# moveWiFi.net
KiCad netlist of a schematic drawn in Altium Designer
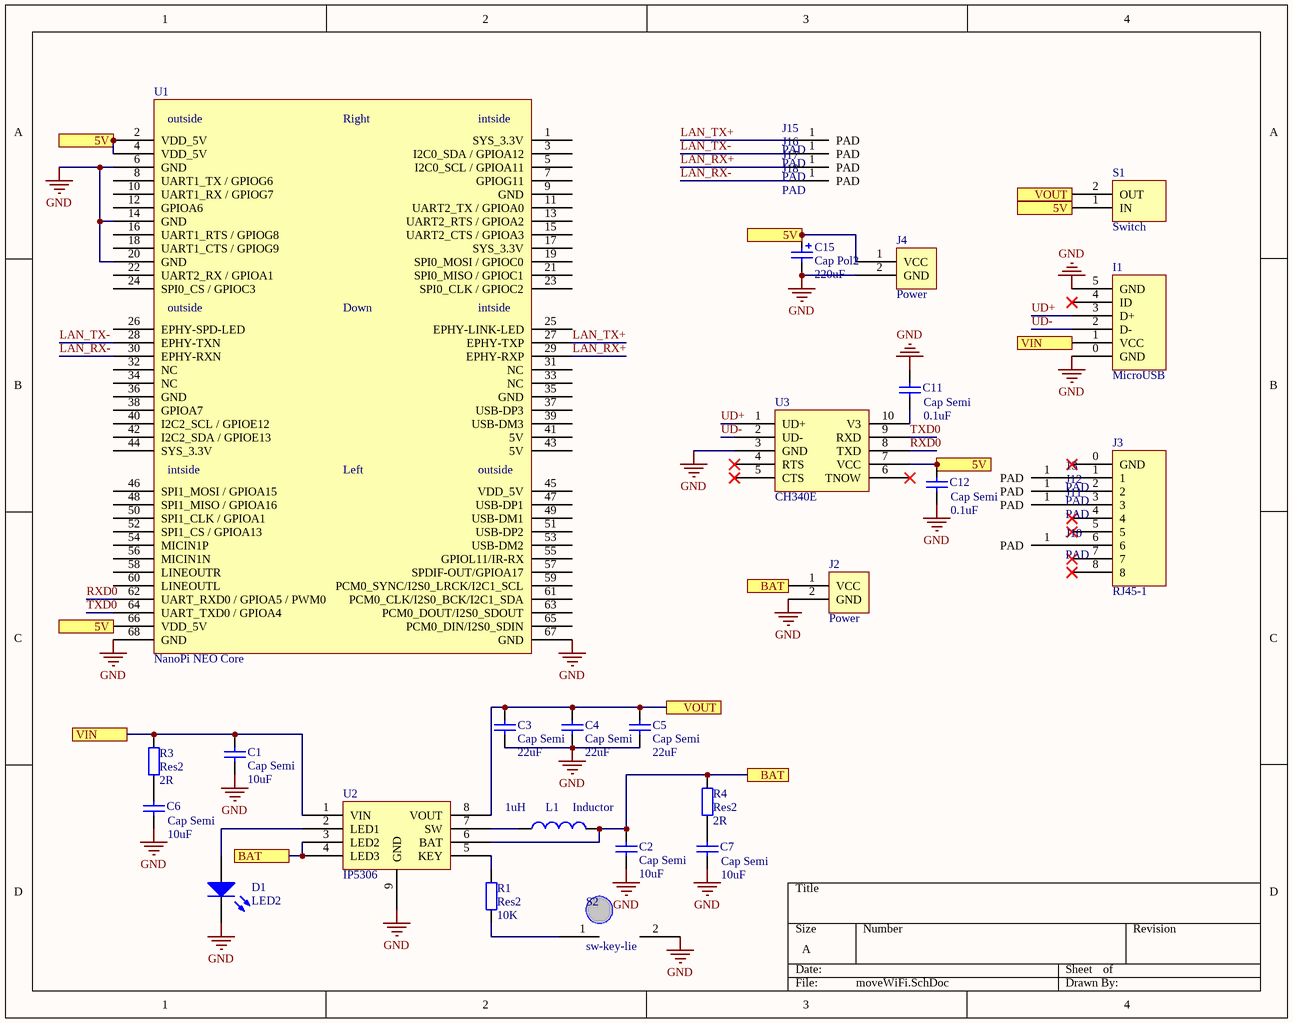
[diagram p0: moveWiFi.SchDoc]

(export (version "E")
  (design (tool "Eeschema 10.0.6"))
  (components
    (comp (ref "13") (value "PAD") (footprint "PAD") (libsource (lib "GavinPCBLib") (part "PAD")))
    (comp (ref "C1")
      (value "Cap Semi")
      (footprint "我的元件库01:C0805")
      (description "Capacitor (Semiconductor SIM Model)")
      (fields (field (name "ALTIUM_VALUE") "10uF") (field (name "PUBLISHER") "Altium Limited"))
      (libsource (lib "Miscellaneous Devices") (part "Cap Semi"))
    )
    (comp (ref "C2")
      (value "Cap Semi")
      (footprint "我的元件库01:C0805")
      (description "Capacitor (Semiconductor SIM Model)")
      (fields (field (name "ALTIUM_VALUE") "10uF") (field (name "PUBLISHER") "Altium Limited"))
      (libsource (lib "Miscellaneous Devices") (part "Cap Semi"))
    )
    (comp (ref "C3")
      (value "Cap Semi")
      (footprint "我的元件库01:C0805")
      (description "Capacitor (Semiconductor SIM Model)")
      (fields (field (name "ALTIUM_VALUE") "22uF") (field (name "PUBLISHER") "Altium Limited"))
      (libsource (lib "Miscellaneous Devices") (part "Cap Semi"))
    )
    (comp (ref "C4")
      (value "Cap Semi")
      (footprint "我的元件库01:C0805")
      (description "Capacitor (Semiconductor SIM Model)")
      (fields (field (name "ALTIUM_VALUE") "22uF") (field (name "PUBLISHER") "Altium Limited"))
      (libsource (lib "Miscellaneous Devices") (part "Cap Semi"))
    )
    (comp (ref "C5")
      (value "Cap Semi")
      (footprint "我的元件库01:C0805")
      (description "Capacitor (Semiconductor SIM Model)")
      (fields (field (name "ALTIUM_VALUE") "22uF") (field (name "PUBLISHER") "Altium Limited"))
      (libsource (lib "Miscellaneous Devices") (part "Cap Semi"))
    )
    (comp (ref "C6")
      (value "Cap Semi")
      (footprint "我的元件库01:C0805")
      (description "Capacitor (Semiconductor SIM Model)")
      (fields (field (name "ALTIUM_VALUE") "10uF") (field (name "PUBLISHER") "Altium Limited"))
      (libsource (lib "Miscellaneous Devices") (part "Cap Semi"))
    )
    (comp (ref "C7")
      (value "Cap Semi")
      (footprint "我的元件库01:C0805")
      (description "Capacitor (Semiconductor SIM Model)")
      (fields (field (name "ALTIUM_VALUE") "10uF") (field (name "PUBLISHER") "Altium Limited"))
      (libsource (lib "Miscellaneous Devices") (part "Cap Semi"))
    )
    (comp (ref "C11")
      (value "Cap Semi")
      (footprint "C0603")
      (description "Capacitor (Semiconductor SIM Model)")
      (fields (field (name "ALTIUM_VALUE") "0.1uF") (field (name "PUBLISHER") "Altium Limited"))
      (libsource (lib "Miscellaneous Devices") (part "Cap Semi"))
    )
    (comp (ref "C12")
      (value "Cap Semi")
      (footprint "C0603")
      (description "Capacitor (Semiconductor SIM Model)")
      (fields (field (name "ALTIUM_VALUE") "0.1uF") (field (name "PUBLISHER") "Altium Limited"))
      (libsource (lib "Miscellaneous Devices") (part "Cap Semi"))
    )
    (comp (ref "C15")
      (value "Cap Pol2")
      (footprint "C7343")
      (description "Polarized Capacitor (Axial)")
      (fields (field (name "ALTIUM_VALUE") "220uF") (field (name "PUBLISHER") "Altium Limited"))
      (libsource (lib "Miscellaneous Devices") (part "Cap Pol2"))
    )
    (comp (ref "D1")
      (value "LED2")
      (footprint "R0603")
      (description "Typical RED, GREEN, YELLOW, AMBER GaAs LED")
      (fields (field (name "PUBLISHER") "Altium Limited"))
      (libsource (lib "Miscellaneous Devices") (part "LED2"))
    )
    (comp (ref "I1")
      (value "MicroUSB")
      (footprint "MicroUSB")
      (libsource (lib "GavinPCBLib") (part "MicroUSB"))
    )
    (comp (ref "J2") (value "Power") (footprint "Power 2") (libsource (lib "GavinPCBLib") (part "Power")))
    (comp (ref "J3") (value "RJ45-1") (footprint "RG45-3") (libsource (lib "GavinPCBLib") (part "RJ45-3")))
    (comp (ref "J4") (value "Power") (footprint "Power 2") (libsource (lib "GavinPCBLib") (part "Power")))
    (comp (ref "J10") (value "PAD") (footprint "PAD") (libsource (lib "GavinPCBLib") (part "PAD")))
    (comp (ref "J11") (value "PAD") (footprint "PAD") (libsource (lib "GavinPCBLib") (part "PAD")))
    (comp (ref "J12") (value "PAD") (footprint "PAD") (libsource (lib "GavinPCBLib") (part "PAD")))
    (comp (ref "J15") (value "PAD") (footprint "PAD") (libsource (lib "GavinPCBLib") (part "PAD")))
    (comp (ref "J16") (value "PAD") (footprint "PAD") (libsource (lib "GavinPCBLib") (part "PAD")))
    (comp (ref "J17") (value "PAD") (footprint "PAD") (libsource (lib "GavinPCBLib") (part "PAD")))
    (comp (ref "J18") (value "PAD") (footprint "PAD") (libsource (lib "GavinPCBLib") (part "PAD")))
    (comp (ref "L1")
      (value "Inductor")
      (footprint "L0630")
      (fields (field (name "ALTIUM_VALUE") "1uH") (field (name "PUBLISHER") "Altium Limited"))
      (libsource (lib "Miscellaneous Devices") (part "Inductor"))
    )
    (comp (ref "R1")
      (value "Res2")
      (footprint "R0603")
      (description "Resistor")
      (fields (field (name "ALTIUM_VALUE") "10K") (field (name "PUBLISHER") "Altium Limited"))
      (libsource (lib "Miscellaneous Devices") (part "Res2"))
    )
    (comp (ref "R3")
      (value "Res2")
      (footprint "R0603")
      (description "Resistor")
      (fields (field (name "ALTIUM_VALUE") "2R") (field (name "PUBLISHER") "Altium Limited"))
      (libsource (lib "Miscellaneous Devices") (part "Res2"))
    )
    (comp (ref "R4")
      (value "Res2")
      (footprint "R0603")
      (description "Resistor")
      (fields (field (name "ALTIUM_VALUE") "2R") (field (name "PUBLISHER") "Altium Limited"))
      (libsource (lib "Miscellaneous Devices") (part "Res2"))
    )
    (comp (ref "S1") (value "Switch") (footprint "SwitchA2") (libsource (lib "GavinPCBLib") (part "Switch2")))
    (comp (ref "S2")
      (value "sw-key-lie")
      (footprint "Key_lie")
      (libsource (lib "GavinPCBLib") (part "sw-key-lie"))
    )
    (comp (ref "U1") (value "NanoPi NEO Core") (libsource (lib "GavinPCBLib") (part "NanoPi_NEO_Core")))
    (comp (ref "U2") (value "IP5306") (footprint "eSOP8") (libsource (lib "GavinPCBLib") (part "IP5306")))
    (comp (ref "U3") (value "CH340E") (footprint "MSOP-10") (libsource (lib "GavinPCBLib") (part "CH340E")))
  )
  (nets
    (net (code "1") (name "/5V") (class "Default")
      (node (ref "C12") (pin "2") (pinfunction "2_2") (pintype "passive"))
      (node (ref "C15") (pin "1") (pinfunction "1_1") (pintype "passive"))
      (node (ref "J4") (pin "1") (pinfunction "VCC_1") (pintype "passive"))
      (node (ref "S1") (pin "1") (pinfunction "IN_1") (pintype "passive"))
      (node (ref "U1") (pin "2") (pinfunction "VDD_5V_2") (pintype "passive"))
      (node (ref "U1") (pin "4") (pinfunction "VDD_5V_4") (pintype "passive"))
      (node (ref "U1") (pin "66") (pinfunction "VDD_5V_66") (pintype "passive"))
      (node (ref "U3") (pin "7") (pinfunction "VCC_7") (pintype "passive"))
    )
    (net (code "2") (name "/BAT") (class "Default")
      (node (ref "C2") (pin "2") (pinfunction "2_2") (pintype "passive"))
      (node (ref "J2") (pin "1") (pinfunction "VCC_1") (pintype "passive"))
      (node (ref "L1") (pin "2") (pinfunction "2_2") (pintype "passive"))
      (node (ref "R4") (pin "2") (pinfunction "2_2") (pintype "passive"))
      (node (ref "U2") (pin "3") (pinfunction "LED2_3") (pintype "passive"))
      (node (ref "U2") (pin "4") (pinfunction "LED3_4") (pintype "passive"))
      (node (ref "U2") (pin "6") (pinfunction "BAT_6") (pintype "passive"))
    )
    (net (code "3") (name "/LAN_RX+") (class "Default")
      (node (ref "J17") (pin "1") (pinfunction "PAD_1") (pintype "passive"))
      (node (ref "U1") (pin "29") (pinfunction "EPHY-RXP_29") (pintype "passive"))
    )
    (net (code "4") (name "/LAN_RX-") (class "Default")
      (node (ref "J18") (pin "1") (pinfunction "PAD_1") (pintype "passive"))
      (node (ref "U1") (pin "30") (pinfunction "EPHY-RXN_30") (pintype "passive"))
    )
    (net (code "5") (name "/LAN_TX+") (class "Default")
      (node (ref "J15") (pin "1") (pinfunction "PAD_1") (pintype "passive"))
      (node (ref "U1") (pin "27") (pinfunction "EPHY-TXP_27") (pintype "passive"))
    )
    (net (code "6") (name "/LAN_TX-") (class "Default")
      (node (ref "J16") (pin "1") (pinfunction "PAD_1") (pintype "passive"))
      (node (ref "U1") (pin "28") (pinfunction "EPHY-TXN_28") (pintype "passive"))
    )
    (net (code "7") (name "/RXD0") (class "Default")
      (node (ref "U1") (pin "62") (pinfunction "UART_RXD0_/_GPIOA5_/_PWM0_62") (pintype "passive"))
      (node (ref "U3") (pin "8") (pinfunction "TXD_8") (pintype "passive"))
    )
    (net (code "8") (name "/TXD0") (class "Default")
      (node (ref "U1") (pin "64") (pinfunction "UART_TXD0_/_GPIOA4_64") (pintype "passive"))
      (node (ref "U3") (pin "9") (pinfunction "RXD_9") (pintype "passive"))
    )
    (net (code "9") (name "/UD+") (class "Default")
      (node (ref "I1") (pin "3") (pinfunction "D+_3") (pintype "passive"))
      (node (ref "U3") (pin "1") (pinfunction "UD+_1") (pintype "passive"))
    )
    (net (code "10") (name "/UD-") (class "Default")
      (node (ref "I1") (pin "2") (pinfunction "D-_2") (pintype "passive"))
      (node (ref "U3") (pin "2") (pinfunction "UD-_2") (pintype "passive"))
    )
    (net (code "11") (name "/VIN") (class "Default")
      (node (ref "C1") (pin "2") (pinfunction "2_2") (pintype "passive"))
      (node (ref "I1") (pin "1") (pinfunction "VCC_1") (pintype "passive"))
      (node (ref "R3") (pin "2") (pinfunction "2_2") (pintype "passive"))
      (node (ref "U2") (pin "1") (pinfunction "VIN_1") (pintype "passive"))
    )
    (net (code "12") (name "/VOUT") (class "Default")
      (node (ref "C3") (pin "2") (pinfunction "2_2") (pintype "passive"))
      (node (ref "C4") (pin "2") (pinfunction "2_2") (pintype "passive"))
      (node (ref "C5") (pin "2") (pinfunction "2_2") (pintype "passive"))
      (node (ref "S1") (pin "2") (pinfunction "OUT_2") (pintype "passive"))
      (node (ref "U2") (pin "8") (pinfunction "VOUT_8") (pintype "passive"))
    )
    (net (code "13") (name "GND") (class "Default")
      (node (ref "C1") (pin "1") (pinfunction "1_1") (pintype "passive"))
      (node (ref "C11") (pin "2") (pinfunction "2_2") (pintype "passive"))
      (node (ref "C12") (pin "1") (pinfunction "1_1") (pintype "passive"))
      (node (ref "C15") (pin "2") (pinfunction "2_2") (pintype "passive"))
      (node (ref "C2") (pin "1") (pinfunction "1_1") (pintype "passive"))
      (node (ref "C3") (pin "1") (pinfunction "1_1") (pintype "passive"))
      (node (ref "C4") (pin "1") (pinfunction "1_1") (pintype "passive"))
      (node (ref "C5") (pin "1") (pinfunction "1_1") (pintype "passive"))
      (node (ref "C6") (pin "1") (pinfunction "1_1") (pintype "passive"))
      (node (ref "C7") (pin "1") (pinfunction "1_1") (pintype "passive"))
      (node (ref "D1") (pin "2") (pinfunction "K_2") (pintype "passive"))
      (node (ref "I1") (pin "0") (pinfunction "GND_0") (pintype "passive"))
      (node (ref "I1") (pin "5") (pinfunction "GND_5") (pintype "passive"))
      (node (ref "J2") (pin "2") (pinfunction "GND_2") (pintype "passive"))
      (node (ref "J4") (pin "2") (pinfunction "GND_2") (pintype "passive"))
      (node (ref "S2") (pin "2") (pintype "passive"))
      (node (ref "U1") (pin "14") (pinfunction "GND_14") (pintype "passive"))
      (node (ref "U1") (pin "20") (pinfunction "GND_20") (pintype "passive"))
      (node (ref "U1") (pin "6") (pinfunction "GND_6") (pintype "passive"))
      (node (ref "U1") (pin "67") (pinfunction "GND_67") (pintype "passive"))
      (node (ref "U1") (pin "68") (pinfunction "GND_68") (pintype "passive"))
      (node (ref "U2") (pin "9") (pinfunction "GND_9") (pintype "passive"))
      (node (ref "U3") (pin "3") (pinfunction "GND_3") (pintype "passive"))
    )
    (net (code "14") (name "Net-(13-PAD)") (class "Default")
      (node (ref "13") (pin "1") (pinfunction "PAD_1") (pintype "passive"))
      (node (ref "J3") (pin "1") (pinfunction "1_1") (pintype "passive"))
    )
    (net (code "15") (name "Net-(C6-Pad2)") (class "Default")
      (node (ref "C6") (pin "2") (pinfunction "2_2") (pintype "passive"))
      (node (ref "R3") (pin "1") (pinfunction "1_1") (pintype "passive"))
    )
    (net (code "16") (name "Net-(C7-Pad2)") (class "Default")
      (node (ref "C7") (pin "2") (pinfunction "2_2") (pintype "passive"))
      (node (ref "R4") (pin "1") (pinfunction "1_1") (pintype "passive"))
    )
    (net (code "17") (name "Net-(D1-A)") (class "Default")
      (node (ref "D1") (pin "1") (pinfunction "A_1") (pintype "passive"))
      (node (ref "U2") (pin "2") (pinfunction "LED1_2") (pintype "passive"))
    )
    (net (code "18") (name "Net-(J10-PAD)") (class "Default")
      (node (ref "J10") (pin "1") (pinfunction "PAD_1") (pintype "passive"))
      (node (ref "J3") (pin "6") (pinfunction "6_6") (pintype "passive"))
    )
    (net (code "19") (name "Net-(J11-PAD)") (class "Default")
      (node (ref "J11") (pin "1") (pinfunction "PAD_1") (pintype "passive"))
      (node (ref "J3") (pin "3") (pinfunction "3_3") (pintype "passive"))
    )
    (net (code "20") (name "Net-(J12-PAD)") (class "Default")
      (node (ref "J12") (pin "1") (pinfunction "PAD_1") (pintype "passive"))
      (node (ref "J3") (pin "2") (pinfunction "2_2") (pintype "passive"))
    )
    (net (code "21") (name "Net-(R1-Pad1)") (class "Default")
      (node (ref "R1") (pin "1") (pinfunction "1_1") (pintype "passive"))
      (node (ref "S2") (pin "1") (pintype "passive"))
    )
    (net (code "22") (name "Net-(U2-KEY)") (class "Default")
      (node (ref "R1") (pin "2") (pinfunction "2_2") (pintype "passive"))
      (node (ref "U2") (pin "5") (pinfunction "KEY_5") (pintype "passive"))
    )
    (net (code "23") (name "Net-(U2-SW)") (class "Default")
      (node (ref "L1") (pin "1") (pinfunction "1_1") (pintype "passive"))
      (node (ref "U2") (pin "7") (pinfunction "SW_7") (pintype "passive"))
    )
    (net (code "24") (name "Net-(U3-V3)") (class "Default")
      (node (ref "C11") (pin "1") (pinfunction "1_1") (pintype "passive"))
      (node (ref "U3") (pin "10") (pinfunction "V3_10") (pintype "passive"))
    )
    (net (code "25") (name "unconnected-(I1-ID-Pad4)") (class "Default")
      (node (ref "I1") (pin "4") (pinfunction "ID_4") (pintype "passive+no_connect"))
    )
    (net (code "26") (name "unconnected-(J3-GND-Pad0)") (class "Default")
      (node (ref "J3") (pin "0") (pinfunction "GND_0") (pintype "passive+no_connect"))
    )
    (net (code "27") (name "unconnected-(J3-Pad4)") (class "Default")
      (node (ref "J3") (pin "4") (pinfunction "4_4") (pintype "passive+no_connect"))
    )
    (net (code "28") (name "unconnected-(J3-Pad5)") (class "Default")
      (node (ref "J3") (pin "5") (pinfunction "5_5") (pintype "passive+no_connect"))
    )
    (net (code "29") (name "unconnected-(J3-Pad7)") (class "Default")
      (node (ref "J3") (pin "7") (pinfunction "7_7") (pintype "passive+no_connect"))
    )
    (net (code "30") (name "unconnected-(J3-Pad8)") (class "Default")
      (node (ref "J3") (pin "8") (pinfunction "8_8") (pintype "passive+no_connect"))
    )
    (net (code "31") (name "unconnected-(U1-5V-Pad41)") (class "Default")
      (node (ref "U1") (pin "41") (pinfunction "5V_41") (pintype "passive"))
    )
    (net (code "32") (name "unconnected-(U1-5V-Pad43)") (class "Default")
      (node (ref "U1") (pin "43") (pinfunction "5V_43") (pintype "passive"))
    )
    (net (code "33") (name "unconnected-(U1-EPHY-LINK-LED-Pad25)") (class "Default")
      (node (ref "U1") (pin "25") (pinfunction "EPHY-LINK-LED_25") (pintype "passive"))
    )
    (net (code "34") (name "unconnected-(U1-EPHY-SPD-LED-Pad26)") (class "Default")
      (node (ref "U1") (pin "26") (pinfunction "EPHY-SPD-LED_26") (pintype "passive"))
    )
    (net (code "35") (name "unconnected-(U1-GND-Pad9)") (class "Default")
      (node (ref "U1") (pin "9") (pinfunction "GND_9") (pintype "passive"))
    )
    (net (code "36") (name "unconnected-(U1-GND-Pad35)") (class "Default")
      (node (ref "U1") (pin "35") (pinfunction "GND_35") (pintype "passive"))
    )
    (net (code "37") (name "unconnected-(U1-GND-Pad36)") (class "Default")
      (node (ref "U1") (pin "36") (pinfunction "GND_36") (pintype "passive"))
    )
    (net (code "38") (name "unconnected-(U1-GPIOA6-Pad12)") (class "Default")
      (node (ref "U1") (pin "12") (pinfunction "GPIOA6_12") (pintype "passive"))
    )
    (net (code "39") (name "unconnected-(U1-GPIOA7-Pad38)") (class "Default")
      (node (ref "U1") (pin "38") (pinfunction "GPIOA7_38") (pintype "passive"))
    )
    (net (code "40") (name "unconnected-(U1-GPIOG11-Pad7)") (class "Default")
      (node (ref "U1") (pin "7") (pinfunction "GPIOG11_7") (pintype "passive"))
    )
    (net (code "41") (name "unconnected-(U1-GPIOL11{slash}IR-RX-Pad55)") (class "Default")
      (node (ref "U1") (pin "55") (pinfunction "GPIOL11/IR-RX_55") (pintype "passive"))
    )
    (net (code "42") (name "unconnected-(U1-I2C0_SCL_{slash}_GPIOA11-Pad5)") (class "Default")
      (node (ref "U1") (pin "5") (pinfunction "I2C0_SCL_/_GPIOA11_5") (pintype "passive"))
    )
    (net (code "43") (name "unconnected-(U1-I2C0_SDA_{slash}_GPIOA12-Pad3)") (class "Default")
      (node (ref "U1") (pin "3") (pinfunction "I2C0_SDA_/_GPIOA12_3") (pintype "passive"))
    )
    (net (code "44") (name "unconnected-(U1-I2C2_SCL_{slash}_GPIOE12-Pad40)") (class "Default")
      (node (ref "U1") (pin "40") (pinfunction "I2C2_SCL_/_GPIOE12_40") (pintype "passive"))
    )
    (net (code "45") (name "unconnected-(U1-I2C2_SDA_{slash}_GPIOE13-Pad42)") (class "Default")
      (node (ref "U1") (pin "42") (pinfunction "I2C2_SDA_/_GPIOE13_42") (pintype "passive"))
    )
    (net (code "46") (name "unconnected-(U1-LINEOUTL-Pad60)") (class "Default")
      (node (ref "U1") (pin "60") (pinfunction "LINEOUTL_60") (pintype "passive"))
    )
    (net (code "47") (name "unconnected-(U1-LINEOUTR-Pad58)") (class "Default")
      (node (ref "U1") (pin "58") (pinfunction "LINEOUTR_58") (pintype "passive"))
    )
    (net (code "48") (name "unconnected-(U1-MICIN1N-Pad56)") (class "Default")
      (node (ref "U1") (pin "56") (pinfunction "MICIN1N_56") (pintype "passive"))
    )
    (net (code "49") (name "unconnected-(U1-MICIN1P-Pad54)") (class "Default")
      (node (ref "U1") (pin "54") (pinfunction "MICIN1P_54") (pintype "passive"))
    )
    (net (code "50") (name "unconnected-(U1-NC-Pad31)") (class "Default")
      (node (ref "U1") (pin "31") (pinfunction "NC_31") (pintype "passive"))
    )
    (net (code "51") (name "unconnected-(U1-NC-Pad32)") (class "Default")
      (node (ref "U1") (pin "32") (pinfunction "NC_32") (pintype "passive"))
    )
    (net (code "52") (name "unconnected-(U1-NC-Pad33)") (class "Default")
      (node (ref "U1") (pin "33") (pinfunction "NC_33") (pintype "passive"))
    )
    (net (code "53") (name "unconnected-(U1-NC-Pad34)") (class "Default")
      (node (ref "U1") (pin "34") (pinfunction "NC_34") (pintype "passive"))
    )
    (net (code "54") (name "unconnected-(U1-PCM0_CLK{slash}I2S0_BCK{slash}I2C1_SDA-Pad61)") (class "Default")
      (node (ref "U1") (pin "61") (pinfunction "PCM0_CLK/I2S0_BCK/I2C1_SDA_61") (pintype "passive"))
    )
    (net (code "55") (name "unconnected-(U1-PCM0_DIN{slash}I2S0_SDIN-Pad65)") (class "Default")
      (node (ref "U1") (pin "65") (pinfunction "PCM0_DIN/I2S0_SDIN_65") (pintype "passive"))
    )
    (net (code "56") (name "unconnected-(U1-PCM0_DOUT{slash}I2S0_SDOUT-Pad63)") (class "Default")
      (node (ref "U1") (pin "63") (pinfunction "PCM0_DOUT/I2S0_SDOUT_63") (pintype "passive"))
    )
    (net (code "57") (name "unconnected-(U1-PCM0_SYNC{slash}I2S0_LRCK{slash}I2C1_SCL-Pad59)") (class "Default")
      (node (ref "U1") (pin "59") (pinfunction "PCM0_SYNC/I2S0_LRCK/I2C1_SCL_59") (pintype "passive"))
    )
    (net (code "58") (name "unconnected-(U1-SPDIF-OUT{slash}GPIOA17-Pad57)") (class "Default")
      (node (ref "U1") (pin "57") (pinfunction "SPDIF-OUT/GPIOA17_57") (pintype "passive"))
    )
    (net (code "59") (name "unconnected-(U1-SPI0_CLK_{slash}_GPIOC2-Pad23)") (class "Default")
      (node (ref "U1") (pin "23") (pinfunction "SPI0_CLK_/_GPIOC2_23") (pintype "passive"))
    )
    (net (code "60") (name "unconnected-(U1-SPI0_CS_{slash}_GPIOC3-Pad24)") (class "Default")
      (node (ref "U1") (pin "24") (pinfunction "SPI0_CS_/_GPIOC3_24") (pintype "passive"))
    )
    (net (code "61") (name "unconnected-(U1-SPI0_MISO_{slash}_GPIOC1-Pad21)") (class "Default")
      (node (ref "U1") (pin "21") (pinfunction "SPI0_MISO_/_GPIOC1_21") (pintype "passive"))
    )
    (net (code "62") (name "unconnected-(U1-SPI0_MOSI_{slash}_GPIOC0-Pad19)") (class "Default")
      (node (ref "U1") (pin "19") (pinfunction "SPI0_MOSI_/_GPIOC0_19") (pintype "passive"))
    )
    (net (code "63") (name "unconnected-(U1-SPI1_CLK_{slash}_GPIOA1-Pad50)") (class "Default")
      (node (ref "U1") (pin "50") (pinfunction "SPI1_CLK_/_GPIOA1_50") (pintype "passive"))
    )
    (net (code "64") (name "unconnected-(U1-SPI1_CS_{slash}_GPIOA13-Pad52)") (class "Default")
      (node (ref "U1") (pin "52") (pinfunction "SPI1_CS_/_GPIOA13_52") (pintype "passive"))
    )
    (net (code "65") (name "unconnected-(U1-SPI1_MISO_{slash}_GPIOA16-Pad48)") (class "Default")
      (node (ref "U1") (pin "48") (pinfunction "SPI1_MISO_/_GPIOA16_48") (pintype "passive"))
    )
    (net (code "66") (name "unconnected-(U1-SPI1_MOSI_{slash}_GPIOA15-Pad46)") (class "Default")
      (node (ref "U1") (pin "46") (pinfunction "SPI1_MOSI_/_GPIOA15_46") (pintype "passive"))
    )
    (net (code "67") (name "unconnected-(U1-SYS_3.3V-Pad1)") (class "Default")
      (node (ref "U1") (pin "1") (pinfunction "SYS_3.3V_1") (pintype "passive"))
    )
    (net (code "68") (name "unconnected-(U1-SYS_3.3V-Pad17)") (class "Default")
      (node (ref "U1") (pin "17") (pinfunction "SYS_3.3V_17") (pintype "passive"))
    )
    (net (code "69") (name "unconnected-(U1-SYS_3.3V-Pad44)") (class "Default")
      (node (ref "U1") (pin "44") (pinfunction "SYS_3.3V_44") (pintype "passive"))
    )
    (net (code "70") (name "unconnected-(U1-UART1_CTS_{slash}_GPIOG9-Pad18)") (class "Default")
      (node (ref "U1") (pin "18") (pinfunction "UART1_CTS_/_GPIOG9_18") (pintype "passive"))
    )
    (net (code "71") (name "unconnected-(U1-UART1_RTS_{slash}_GPIOG8-Pad16)") (class "Default")
      (node (ref "U1") (pin "16") (pinfunction "UART1_RTS_/_GPIOG8_16") (pintype "passive"))
    )
    (net (code "72") (name "unconnected-(U1-UART1_RX_{slash}_GPIOG7-Pad10)") (class "Default")
      (node (ref "U1") (pin "10") (pinfunction "UART1_RX_/_GPIOG7_10") (pintype "passive"))
    )
    (net (code "73") (name "unconnected-(U1-UART1_TX_{slash}_GPIOG6-Pad8)") (class "Default")
      (node (ref "U1") (pin "8") (pinfunction "UART1_TX_/_GPIOG6_8") (pintype "passive"))
    )
    (net (code "74") (name "unconnected-(U1-UART2_CTS_{slash}_GPIOA3-Pad15)") (class "Default")
      (node (ref "U1") (pin "15") (pinfunction "UART2_CTS_/_GPIOA3_15") (pintype "passive"))
    )
    (net (code "75") (name "unconnected-(U1-UART2_RTS_{slash}_GPIOA2-Pad13)") (class "Default")
      (node (ref "U1") (pin "13") (pinfunction "UART2_RTS_/_GPIOA2_13") (pintype "passive"))
    )
    (net (code "76") (name "unconnected-(U1-UART2_RX_{slash}_GPIOA1-Pad22)") (class "Default")
      (node (ref "U1") (pin "22") (pinfunction "UART2_RX_/_GPIOA1_22") (pintype "passive"))
    )
    (net (code "77") (name "unconnected-(U1-UART2_TX_{slash}_GPIOA0-Pad11)") (class "Default")
      (node (ref "U1") (pin "11") (pinfunction "UART2_TX_/_GPIOA0_11") (pintype "passive"))
    )
    (net (code "78") (name "unconnected-(U1-USB-DM1-Pad49)") (class "Default")
      (node (ref "U1") (pin "49") (pinfunction "USB-DM1_49") (pintype "passive"))
    )
    (net (code "79") (name "unconnected-(U1-USB-DM2-Pad53)") (class "Default")
      (node (ref "U1") (pin "53") (pinfunction "USB-DM2_53") (pintype "passive"))
    )
    (net (code "80") (name "unconnected-(U1-USB-DM3-Pad39)") (class "Default")
      (node (ref "U1") (pin "39") (pinfunction "USB-DM3_39") (pintype "passive"))
    )
    (net (code "81") (name "unconnected-(U1-USB-DP1-Pad47)") (class "Default")
      (node (ref "U1") (pin "47") (pinfunction "USB-DP1_47") (pintype "passive"))
    )
    (net (code "82") (name "unconnected-(U1-USB-DP2-Pad51)") (class "Default")
      (node (ref "U1") (pin "51") (pinfunction "USB-DP2_51") (pintype "passive"))
    )
    (net (code "83") (name "unconnected-(U1-USB-DP3-Pad37)") (class "Default")
      (node (ref "U1") (pin "37") (pinfunction "USB-DP3_37") (pintype "passive"))
    )
    (net (code "84") (name "unconnected-(U1-VDD_5V-Pad45)") (class "Default")
      (node (ref "U1") (pin "45") (pinfunction "VDD_5V_45") (pintype "passive"))
    )
    (net (code "85") (name "unconnected-(U3-CTS-Pad5)") (class "Default")
      (node (ref "U3") (pin "5") (pinfunction "CTS_5") (pintype "passive+no_connect"))
    )
    (net (code "86") (name "unconnected-(U3-RTS-Pad4)") (class "Default")
      (node (ref "U3") (pin "4") (pinfunction "RTS_4") (pintype "passive+no_connect"))
    )
    (net (code "87") (name "unconnected-(U3-TNOW-Pad6)") (class "Default")
      (node (ref "U3") (pin "6") (pinfunction "TNOW_6") (pintype "passive+no_connect"))
    )
  )
)
